# BMS_Slave_Top.net
KiCad netlist of a schematic drawn in Altium Designer
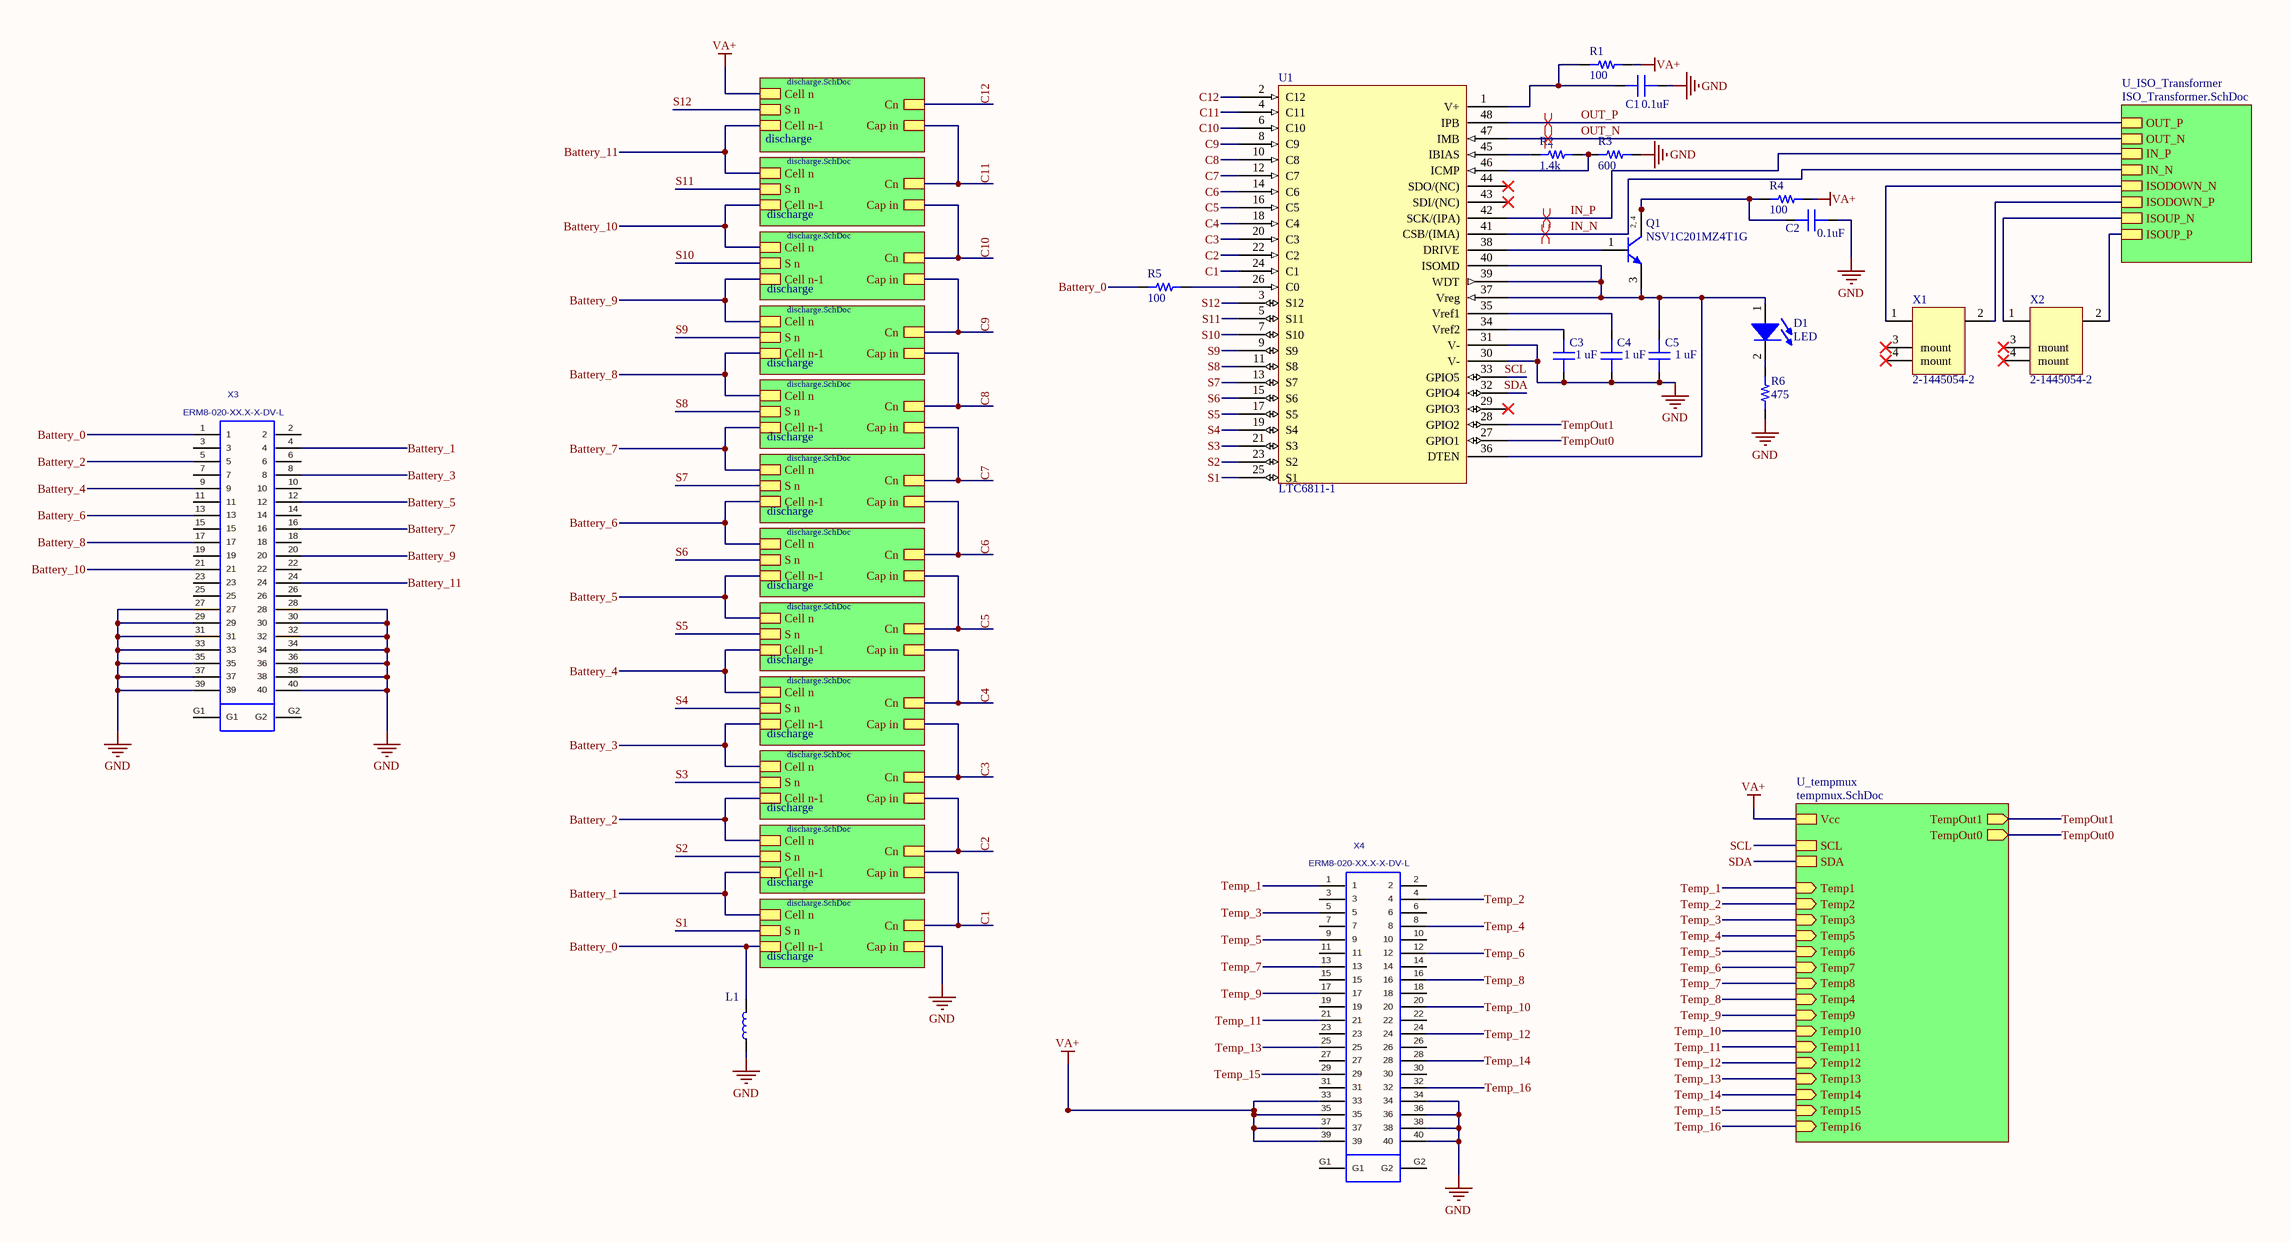
[diagram p0: BMS_Slave_Top.SchDoc]

(export (version "E")
  (design (tool "Eeschema 10.0.6"))
  (components
    (comp (ref "C1")
      (value "capacitor")
      (footprint "0603")
      (description "Generic 0603 capacitor")
      (fields (field (name "CAPACITANCE") "0.1uF") (field (name "VOLTAGE") "50"))
      (libsource (lib "altlib") (part "capacitor"))
    )
    (comp (ref "C2")
      (value "capacitor")
      (footprint "0603")
      (description "Generic 0603 capacitor")
      (fields (field (name "CAPACITANCE") "0.1uF") (field (name "VOLTAGE") "50"))
      (libsource (lib "altlib") (part "capacitor"))
    )
    (comp (ref "C3")
      (value "capacitor")
      (footprint "0603")
      (description "Generic 0603 capacitor")
      (fields (field (name "CAPACITANCE") "1 uF") (field (name "VOLTAGE") "50"))
      (libsource (lib "altlib") (part "capacitor"))
    )
    (comp (ref "C4")
      (value "capacitor")
      (footprint "0603")
      (description "Generic 0603 capacitor")
      (fields (field (name "CAPACITANCE") "1 uF") (field (name "VOLTAGE") "50"))
      (libsource (lib "altlib") (part "capacitor"))
    )
    (comp (ref "C5")
      (value "capacitor")
      (footprint "0603")
      (description "Generic 0603 capacitor")
      (fields (field (name "CAPACITANCE") "1 uF") (field (name "VOLTAGE") "50"))
      (libsource (lib "altlib") (part "capacitor"))
    )
    (comp (ref "D1")
      (value "LED")
      (footprint "0805_LED")
      (description "Generic 0805 LED")
      (libsource (lib "altlib") (part "LED"))
    )
    (comp (ref "L1")
      (value "MPZ1608S221ATA00")
      (footprint "0603")
      (description "220 Ohms @ 100MHz 1 Power Line Ferrite Bead 0")
      (fields
        (field (name "DIGI-KEY_PART_NUMBER") "445-1565-1-ND")
        (field (name "MF") "TDK")
        (field (name "CREATEDBY") "Kevin")
      )
      (libsource (lib "altlib") (part "MPZ1608S221ATA00"))
    )
    (comp (ref "Q1")
      (value "NSV1C201MZ4T1G")
      (footprint "ONSC-SOT-223-4-318E-04_V")
      (fields (field (name "MANUFACTURER") "On Semiconductor") (field (name "CREATEDBY") "J.Childers"))
      (libsource (lib "altlib") (part "CMP-1048-00450-1"))
    )
    (comp (ref "R1")
      (value "100")
      (footprint "RES 0603/1608")
      (fields (field (name "RESISTANCE") "100"))
      (libsource (lib "altlib") (part "Resistor"))
    )
    (comp (ref "R2")
      (value "1.4k")
      (footprint "RES 0603/1608")
      (fields (field (name "RESISTANCE") "1.4k"))
      (libsource (lib "altlib") (part "Resistor"))
    )
    (comp (ref "R3")
      (value "600")
      (footprint "RES 0603/1608")
      (fields (field (name "RESISTANCE") "600"))
      (libsource (lib "altlib") (part "Resistor"))
    )
    (comp (ref "R4")
      (value "100")
      (footprint "RES 0603/1608")
      (fields (field (name "RESISTANCE") "100"))
      (libsource (lib "altlib") (part "Resistor"))
    )
    (comp (ref "R5")
      (value "100")
      (footprint "RES 0603/1608")
      (fields (field (name "RESISTANCE") "100"))
      (libsource (lib "altlib") (part "Resistor"))
    )
    (comp (ref "R6")
      (value "475")
      (footprint "RES 0603/1608")
      (fields (field (name "RESISTANCE") "475"))
      (libsource (lib "altlib") (part "Resistor"))
    )
    (comp (ref "U1")
      (value "LTC6811-1")
      (footprint "LTC6811-1")
      (libsource (lib "altlib") (part "LTC6811-1"))
    )
    (comp (ref "X1")
      (value "2-1445054-2")
      (footprint "2-1445054-2")
      (description "Micro MATE-N-LOK 1x2")
      (libsource (lib "altlib") (part "2-1445054-2"))
    )
    (comp (ref "X2")
      (value "2-1445054-2")
      (footprint "2-1445054-2")
      (description "Micro MATE-N-LOK 1x2")
      (libsource (lib "altlib") (part "2-1445054-2"))
    )
    (comp (ref "X3")
      (value "ERM8-020-XX.X-X-DV-L")
      (footprint "ERM8-020-XX.X-X-DV-L")
      (fields (field (name "MANUFACTURER") "SAMTEC") (field (name "CREATED") "August 17, 2016 - Wendy Xin"))
      (libsource (lib "altlib") (part "ERM8-020-XX.X-X-DV-L"))
    )
    (comp (ref "X4")
      (value "ERM8-020-XX.X-X-DV-L")
      (footprint "ERM8-020-XX.X-X-DV-L")
      (fields (field (name "MANUFACTURER") "SAMTEC") (field (name "CREATED") "August 17, 2016 - Wendy Xin"))
      (libsource (lib "altlib") (part "ERM8-020-XX.X-X-DV-L"))
    )
  )
  (nets
    (net (code "1") (name "/Battery_0") (class "Default")
      (node (ref "L1") (pin "2") (pinfunction "2_2") (pintype "passive"))
      (node (ref "R5") (pin "1") (pinfunction "1_1") (pintype "passive"))
      (node (ref "X3") (pin "1") (pinfunction "1_1") (pintype "passive"))
    )
    (net (code "2") (name "/Battery_1") (class "Default")
      (node (ref "X3") (pin "4") (pinfunction "4_4") (pintype "passive"))
    )
    (net (code "3") (name "/Battery_2") (class "Default")
      (node (ref "X3") (pin "5") (pinfunction "5_5") (pintype "passive"))
    )
    (net (code "4") (name "/Battery_3") (class "Default")
      (node (ref "X3") (pin "8") (pinfunction "8_8") (pintype "passive"))
    )
    (net (code "5") (name "/Battery_4") (class "Default")
      (node (ref "X3") (pin "9") (pinfunction "9_9") (pintype "passive"))
    )
    (net (code "6") (name "/Battery_5") (class "Default")
      (node (ref "X3") (pin "12") (pinfunction "12_12") (pintype "passive"))
    )
    (net (code "7") (name "/Battery_6") (class "Default")
      (node (ref "X3") (pin "13") (pinfunction "13_13") (pintype "passive"))
    )
    (net (code "8") (name "/Battery_7") (class "Default")
      (node (ref "X3") (pin "16") (pinfunction "16_16") (pintype "passive"))
    )
    (net (code "9") (name "/Battery_8") (class "Default")
      (node (ref "X3") (pin "17") (pinfunction "17_17") (pintype "passive"))
    )
    (net (code "10") (name "/Battery_9") (class "Default")
      (node (ref "X3") (pin "20") (pinfunction "20_20") (pintype "passive"))
    )
    (net (code "11") (name "/Battery_10") (class "Default")
      (node (ref "X3") (pin "21") (pinfunction "21_21") (pintype "passive"))
    )
    (net (code "12") (name "/Battery_11") (class "Default")
      (node (ref "X3") (pin "24") (pinfunction "24_24") (pintype "passive"))
    )
    (net (code "13") (name "/C1") (class "Default")
      (node (ref "U1") (pin "24") (pinfunction "C1_24") (pintype "input"))
    )
    (net (code "14") (name "/C2") (class "Default")
      (node (ref "U1") (pin "22") (pinfunction "C2_22") (pintype "input"))
    )
    (net (code "15") (name "/C3") (class "Default")
      (node (ref "U1") (pin "20") (pinfunction "C3_20") (pintype "input"))
    )
    (net (code "16") (name "/C4") (class "Default")
      (node (ref "U1") (pin "18") (pinfunction "C4_18") (pintype "input"))
    )
    (net (code "17") (name "/C5") (class "Default")
      (node (ref "U1") (pin "16") (pinfunction "C5_16") (pintype "input"))
    )
    (net (code "18") (name "/C6") (class "Default")
      (node (ref "U1") (pin "14") (pinfunction "C6_14") (pintype "input"))
    )
    (net (code "19") (name "/C7") (class "Default")
      (node (ref "U1") (pin "12") (pinfunction "C7_12") (pintype "input"))
    )
    (net (code "20") (name "/C8") (class "Default")
      (node (ref "U1") (pin "10") (pinfunction "C8_10") (pintype "input"))
    )
    (net (code "21") (name "/C9") (class "Default")
      (node (ref "U1") (pin "8") (pinfunction "C9_8") (pintype "input"))
    )
    (net (code "22") (name "/C10") (class "Default")
      (node (ref "U1") (pin "6") (pinfunction "C10_6") (pintype "input"))
    )
    (net (code "23") (name "/C11") (class "Default")
      (node (ref "U1") (pin "4") (pinfunction "C11_4") (pintype "input"))
    )
    (net (code "24") (name "/C12") (class "Default")
      (node (ref "U1") (pin "2") (pinfunction "C12_2") (pintype "input"))
    )
    (net (code "25") (name "/IN_N") (class "Default")
      (node (ref "U1") (pin "41") (pinfunction "CSB/(IMA)_41") (pintype "passive"))
    )
    (net (code "26") (name "/IN_P") (class "Default")
      (node (ref "U1") (pin "42") (pinfunction "SCK/(IPA)_42") (pintype "passive"))
    )
    (net (code "27") (name "/ISODOWN_N") (class "Default") (node (ref "X1") (pin "1") (pintype "power_in")))
    (net (code "28") (name "/ISODOWN_P") (class "Default") (node (ref "X1") (pin "2") (pintype "power_in")))
    (net (code "29") (name "/ISOUP_N") (class "Default") (node (ref "X2") (pin "1") (pintype "power_in")))
    (net (code "30") (name "/ISOUP_P") (class "Default") (node (ref "X2") (pin "2") (pintype "power_in")))
    (net (code "31") (name "/OUT_N") (class "Default")
      (node (ref "U1") (pin "47") (pinfunction "IMB_47") (pintype "input"))
    )
    (net (code "32") (name "/OUT_P") (class "Default")
      (node (ref "U1") (pin "48") (pinfunction "IPB_48") (pintype "passive"))
    )
    (net (code "33") (name "/S1") (class "Default")
      (node (ref "U1") (pin "25") (pinfunction "S1_25") (pintype "bidirectional"))
    )
    (net (code "34") (name "/S2") (class "Default")
      (node (ref "U1") (pin "23") (pinfunction "S2_23") (pintype "bidirectional"))
    )
    (net (code "35") (name "/S3") (class "Default")
      (node (ref "U1") (pin "21") (pinfunction "S3_21") (pintype "bidirectional"))
    )
    (net (code "36") (name "/S4") (class "Default")
      (node (ref "U1") (pin "19") (pinfunction "S4_19") (pintype "bidirectional"))
    )
    (net (code "37") (name "/S5") (class "Default")
      (node (ref "U1") (pin "17") (pinfunction "S5_17") (pintype "bidirectional"))
    )
    (net (code "38") (name "/S6") (class "Default")
      (node (ref "U1") (pin "15") (pinfunction "S6_15") (pintype "bidirectional"))
    )
    (net (code "39") (name "/S7") (class "Default")
      (node (ref "U1") (pin "13") (pinfunction "S7_13") (pintype "bidirectional"))
    )
    (net (code "40") (name "/S8") (class "Default")
      (node (ref "U1") (pin "11") (pinfunction "S8_11") (pintype "bidirectional"))
    )
    (net (code "41") (name "/S9") (class "Default")
      (node (ref "U1") (pin "9") (pinfunction "S9_9") (pintype "bidirectional"))
    )
    (net (code "42") (name "/S10") (class "Default")
      (node (ref "U1") (pin "7") (pinfunction "S10_7") (pintype "bidirectional"))
    )
    (net (code "43") (name "/S11") (class "Default")
      (node (ref "U1") (pin "5") (pinfunction "S11_5") (pintype "bidirectional"))
    )
    (net (code "44") (name "/S12") (class "Default")
      (node (ref "U1") (pin "3") (pinfunction "S12_3") (pintype "bidirectional"))
    )
    (net (code "45") (name "/SCL") (class "Default")
      (node (ref "U1") (pin "33") (pinfunction "GPIO5_33") (pintype "bidirectional"))
    )
    (net (code "46") (name "/SDA") (class "Default")
      (node (ref "U1") (pin "32") (pinfunction "GPIO4_32") (pintype "bidirectional"))
    )
    (net (code "47") (name "/TempOut0") (class "Default")
      (node (ref "U1") (pin "27") (pinfunction "GPIO1_27") (pintype "bidirectional"))
    )
    (net (code "48") (name "/TempOut1") (class "Default")
      (node (ref "U1") (pin "28") (pinfunction "GPIO2_28") (pintype "bidirectional"))
    )
    (net (code "49") (name "/Temp_1") (class "Default")
      (node (ref "X4") (pin "1") (pinfunction "1_1") (pintype "passive"))
    )
    (net (code "50") (name "/Temp_2") (class "Default")
      (node (ref "X4") (pin "4") (pinfunction "4_4") (pintype "passive"))
    )
    (net (code "51") (name "/Temp_3") (class "Default")
      (node (ref "X4") (pin "5") (pinfunction "5_5") (pintype "passive"))
    )
    (net (code "52") (name "/Temp_4") (class "Default")
      (node (ref "X4") (pin "8") (pinfunction "8_8") (pintype "passive"))
    )
    (net (code "53") (name "/Temp_5") (class "Default")
      (node (ref "X4") (pin "9") (pinfunction "9_9") (pintype "passive"))
    )
    (net (code "54") (name "/Temp_6") (class "Default")
      (node (ref "X4") (pin "12") (pinfunction "12_12") (pintype "passive"))
    )
    (net (code "55") (name "/Temp_7") (class "Default")
      (node (ref "X4") (pin "13") (pinfunction "13_13") (pintype "passive"))
    )
    (net (code "56") (name "/Temp_8") (class "Default")
      (node (ref "X4") (pin "16") (pinfunction "16_16") (pintype "passive"))
    )
    (net (code "57") (name "/Temp_9") (class "Default")
      (node (ref "X4") (pin "17") (pinfunction "17_17") (pintype "passive"))
    )
    (net (code "58") (name "/Temp_10") (class "Default")
      (node (ref "X4") (pin "20") (pinfunction "20_20") (pintype "passive"))
    )
    (net (code "59") (name "/Temp_11") (class "Default")
      (node (ref "X4") (pin "21") (pinfunction "21_21") (pintype "passive"))
    )
    (net (code "60") (name "/Temp_12") (class "Default")
      (node (ref "X4") (pin "24") (pinfunction "24_24") (pintype "passive"))
    )
    (net (code "61") (name "/Temp_13") (class "Default")
      (node (ref "X4") (pin "25") (pinfunction "25_25") (pintype "passive"))
    )
    (net (code "62") (name "/Temp_14") (class "Default")
      (node (ref "X4") (pin "28") (pinfunction "28_28") (pintype "passive"))
    )
    (net (code "63") (name "/Temp_15") (class "Default")
      (node (ref "X4") (pin "29") (pinfunction "29_29") (pintype "passive"))
    )
    (net (code "64") (name "/Temp_16") (class "Default")
      (node (ref "X4") (pin "32") (pinfunction "32_32") (pintype "passive"))
    )
    (net (code "65") (name "GND") (class "Default")
      (node (ref "C1") (pin "1") (pinfunction "1_1") (pintype "passive"))
      (node (ref "C2") (pin "1") (pinfunction "1_1") (pintype "passive"))
      (node (ref "C3") (pin "1") (pinfunction "1_1") (pintype "passive"))
      (node (ref "C4") (pin "1") (pinfunction "1_1") (pintype "passive"))
      (node (ref "C5") (pin "1") (pinfunction "1_1") (pintype "passive"))
      (node (ref "L1") (pin "1") (pinfunction "1_1") (pintype "passive"))
      (node (ref "R3") (pin "2") (pinfunction "2_2") (pintype "passive"))
      (node (ref "R6") (pin "1") (pinfunction "1_1") (pintype "passive"))
      (node (ref "U1") (pin "30") (pinfunction "V-_30") (pintype "power_in"))
      (node (ref "U1") (pin "31") (pinfunction "V-_31") (pintype "power_in"))
      (node (ref "X3") (pin "27") (pinfunction "27_27") (pintype "passive"))
      (node (ref "X3") (pin "28") (pinfunction "28_28") (pintype "passive"))
      (node (ref "X3") (pin "29") (pinfunction "29_29") (pintype "passive"))
      (node (ref "X3") (pin "30") (pinfunction "30_30") (pintype "passive"))
      (node (ref "X3") (pin "31") (pinfunction "31_31") (pintype "passive"))
      (node (ref "X3") (pin "32") (pinfunction "32_32") (pintype "passive"))
      (node (ref "X3") (pin "33") (pinfunction "33_33") (pintype "passive"))
      (node (ref "X3") (pin "34") (pinfunction "34_34") (pintype "passive"))
      (node (ref "X3") (pin "35") (pinfunction "35_35") (pintype "passive"))
      (node (ref "X3") (pin "36") (pinfunction "36_36") (pintype "passive"))
      (node (ref "X3") (pin "37") (pinfunction "37_37") (pintype "passive"))
      (node (ref "X3") (pin "38") (pinfunction "38_38") (pintype "passive"))
      (node (ref "X3") (pin "39") (pinfunction "39_39") (pintype "passive"))
      (node (ref "X3") (pin "40") (pinfunction "40_40") (pintype "passive"))
      (node (ref "X4") (pin "34") (pinfunction "34_34") (pintype "passive"))
      (node (ref "X4") (pin "36") (pinfunction "36_36") (pintype "passive"))
      (node (ref "X4") (pin "38") (pinfunction "38_38") (pintype "passive"))
      (node (ref "X4") (pin "40") (pinfunction "40_40") (pintype "passive"))
    )
    (net (code "66") (name "Net-(C2-Pad2)") (class "Default")
      (node (ref "C2") (pin "2") (pinfunction "2_2") (pintype "passive"))
      (node (ref "Q1") (pin "2") (pinfunction "C_2") (pintype "passive"))
      (node (ref "Q1") (pin "4") (pinfunction "C_4") (pintype "passive"))
      (node (ref "R4") (pin "2") (pinfunction "2_2") (pintype "passive"))
    )
    (net (code "67") (name "Net-(D1-A)") (class "Default")
      (node (ref "C5") (pin "2") (pinfunction "2_2") (pintype "passive"))
      (node (ref "D1") (pin "1") (pinfunction "A_1") (pintype "passive"))
      (node (ref "Q1") (pin "3") (pinfunction "E_3") (pintype "passive"))
      (node (ref "U1") (pin "36") (pinfunction "DTEN_36") (pintype "passive"))
      (node (ref "U1") (pin "37") (pinfunction "Vreg_37") (pintype "input"))
      (node (ref "U1") (pin "39") (pinfunction "WDT_39") (pintype "output"))
      (node (ref "U1") (pin "40") (pinfunction "ISOMD_40") (pintype "passive"))
    )
    (net (code "68") (name "Net-(D1-K)") (class "Default")
      (node (ref "D1") (pin "2") (pinfunction "K_2") (pintype "passive"))
      (node (ref "R6") (pin "2") (pinfunction "2_2") (pintype "passive"))
    )
    (net (code "69") (name "Net-(Q1-B)") (class "Default")
      (node (ref "Q1") (pin "1") (pinfunction "B_1") (pintype "passive"))
      (node (ref "U1") (pin "38") (pinfunction "DRIVE_38") (pintype "passive"))
    )
    (net (code "70") (name "Net-(U1-C0)") (class "Default")
      (node (ref "R5") (pin "2") (pinfunction "2_2") (pintype "passive"))
      (node (ref "U1") (pin "26") (pinfunction "C0_26") (pintype "input"))
    )
    (net (code "71") (name "Net-(U1-IBIAS)") (class "Default")
      (node (ref "R2") (pin "1") (pinfunction "1_1") (pintype "passive"))
      (node (ref "U1") (pin "45") (pinfunction "IBIAS_45") (pintype "input"))
    )
    (net (code "72") (name "Net-(U1-ICMP)") (class "Default")
      (node (ref "R2") (pin "2") (pinfunction "2_2") (pintype "passive"))
      (node (ref "R3") (pin "1") (pinfunction "1_1") (pintype "passive"))
      (node (ref "U1") (pin "46") (pinfunction "ICMP_46") (pintype "input"))
    )
    (net (code "73") (name "Net-(U1-V+)") (class "Default")
      (node (ref "C1") (pin "2") (pinfunction "2_2") (pintype "passive"))
      (node (ref "R1") (pin "2") (pinfunction "2_2") (pintype "passive"))
      (node (ref "U1") (pin "1") (pinfunction "V+_1") (pintype "power_in"))
    )
    (net (code "74") (name "Net-(U1-Vref1)") (class "Default")
      (node (ref "C4") (pin "2") (pinfunction "2_2") (pintype "passive"))
      (node (ref "U1") (pin "35") (pinfunction "Vref1_35") (pintype "passive"))
    )
    (net (code "75") (name "Net-(U1-Vref2)") (class "Default")
      (node (ref "C3") (pin "2") (pinfunction "2_2") (pintype "passive"))
      (node (ref "U1") (pin "34") (pinfunction "Vref2_34") (pintype "passive"))
    )
    (net (code "76") (name "VA+") (class "Default")
      (node (ref "R1") (pin "1") (pinfunction "1_1") (pintype "passive"))
      (node (ref "R4") (pin "1") (pinfunction "1_1") (pintype "passive"))
      (node (ref "X4") (pin "33") (pinfunction "33_33") (pintype "passive"))
      (node (ref "X4") (pin "35") (pinfunction "35_35") (pintype "passive"))
      (node (ref "X4") (pin "37") (pinfunction "37_37") (pintype "passive"))
      (node (ref "X4") (pin "39") (pinfunction "39_39") (pintype "passive"))
    )
    (net (code "77") (name "unconnected-(U1-GPIO3-Pad29)") (class "Default")
      (node (ref "U1") (pin "29") (pinfunction "GPIO3_29") (pintype "bidirectional+no_connect"))
    )
    (net (code "78") (name "unconnected-(U1-SDI{slash}(NC)-Pad43)") (class "Default")
      (node (ref "U1") (pin "43") (pinfunction "SDI/(NC)_43") (pintype "passive+no_connect"))
    )
    (net (code "79") (name "unconnected-(U1-SDO{slash}(NC)-Pad44)") (class "Default")
      (node (ref "U1") (pin "44") (pinfunction "SDO/(NC)_44") (pintype "passive+no_connect"))
    )
    (net (code "80") (name "unconnected-(X1-mount-Pad3)") (class "Default")
      (node (ref "X1") (pin "3") (pinfunction "mount_3") (pintype "power_in+no_connect"))
    )
    (net (code "81") (name "unconnected-(X1-mount-Pad4)") (class "Default")
      (node (ref "X1") (pin "4") (pinfunction "mount_4") (pintype "power_in+no_connect"))
    )
    (net (code "82") (name "unconnected-(X2-mount-Pad3)") (class "Default")
      (node (ref "X2") (pin "3") (pinfunction "mount_3") (pintype "power_in+no_connect"))
    )
    (net (code "83") (name "unconnected-(X2-mount-Pad4)") (class "Default")
      (node (ref "X2") (pin "4") (pinfunction "mount_4") (pintype "power_in+no_connect"))
    )
    (net (code "84") (name "unconnected-(X3-Pad2)") (class "Default")
      (node (ref "X3") (pin "2") (pinfunction "2_2") (pintype "passive"))
    )
    (net (code "85") (name "unconnected-(X3-Pad3)") (class "Default")
      (node (ref "X3") (pin "3") (pinfunction "3_3") (pintype "passive"))
    )
    (net (code "86") (name "unconnected-(X3-Pad6)") (class "Default")
      (node (ref "X3") (pin "6") (pinfunction "6_6") (pintype "passive"))
    )
    (net (code "87") (name "unconnected-(X3-Pad7)") (class "Default")
      (node (ref "X3") (pin "7") (pinfunction "7_7") (pintype "passive"))
    )
    (net (code "88") (name "unconnected-(X3-Pad10)") (class "Default")
      (node (ref "X3") (pin "10") (pinfunction "10_10") (pintype "passive"))
    )
    (net (code "89") (name "unconnected-(X3-Pad11)") (class "Default")
      (node (ref "X3") (pin "11") (pinfunction "11_11") (pintype "passive"))
    )
    (net (code "90") (name "unconnected-(X3-Pad14)") (class "Default")
      (node (ref "X3") (pin "14") (pinfunction "14_14") (pintype "passive"))
    )
    (net (code "91") (name "unconnected-(X3-Pad15)") (class "Default")
      (node (ref "X3") (pin "15") (pinfunction "15_15") (pintype "passive"))
    )
    (net (code "92") (name "unconnected-(X3-Pad18)") (class "Default")
      (node (ref "X3") (pin "18") (pinfunction "18_18") (pintype "passive"))
    )
    (net (code "93") (name "unconnected-(X3-Pad19)") (class "Default")
      (node (ref "X3") (pin "19") (pinfunction "19_19") (pintype "passive"))
    )
    (net (code "94") (name "unconnected-(X3-Pad22)") (class "Default")
      (node (ref "X3") (pin "22") (pinfunction "22_22") (pintype "passive"))
    )
    (net (code "95") (name "unconnected-(X3-Pad23)") (class "Default")
      (node (ref "X3") (pin "23") (pinfunction "23_23") (pintype "passive"))
    )
    (net (code "96") (name "unconnected-(X3-Pad25)") (class "Default")
      (node (ref "X3") (pin "25") (pinfunction "25_25") (pintype "passive"))
    )
    (net (code "97") (name "unconnected-(X3-Pad26)") (class "Default")
      (node (ref "X3") (pin "26") (pinfunction "26_26") (pintype "passive"))
    )
    (net (code "98") (name "unconnected-(X3-PadG1)") (class "Default")
      (node (ref "X3") (pin "G1") (pinfunction "G1_G1") (pintype "passive"))
    )
    (net (code "99") (name "unconnected-(X3-PadG2)") (class "Default")
      (node (ref "X3") (pin "G2") (pinfunction "G2_G2") (pintype "passive"))
    )
    (net (code "100") (name "unconnected-(X4-Pad2)") (class "Default")
      (node (ref "X4") (pin "2") (pinfunction "2_2") (pintype "passive"))
    )
    (net (code "101") (name "unconnected-(X4-Pad3)") (class "Default")
      (node (ref "X4") (pin "3") (pinfunction "3_3") (pintype "passive"))
    )
    (net (code "102") (name "unconnected-(X4-Pad6)") (class "Default")
      (node (ref "X4") (pin "6") (pinfunction "6_6") (pintype "passive"))
    )
    (net (code "103") (name "unconnected-(X4-Pad7)") (class "Default")
      (node (ref "X4") (pin "7") (pinfunction "7_7") (pintype "passive"))
    )
    (net (code "104") (name "unconnected-(X4-Pad10)") (class "Default")
      (node (ref "X4") (pin "10") (pinfunction "10_10") (pintype "passive"))
    )
    (net (code "105") (name "unconnected-(X4-Pad11)") (class "Default")
      (node (ref "X4") (pin "11") (pinfunction "11_11") (pintype "passive"))
    )
    (net (code "106") (name "unconnected-(X4-Pad14)") (class "Default")
      (node (ref "X4") (pin "14") (pinfunction "14_14") (pintype "passive"))
    )
    (net (code "107") (name "unconnected-(X4-Pad15)") (class "Default")
      (node (ref "X4") (pin "15") (pinfunction "15_15") (pintype "passive"))
    )
    (net (code "108") (name "unconnected-(X4-Pad18)") (class "Default")
      (node (ref "X4") (pin "18") (pinfunction "18_18") (pintype "passive"))
    )
    (net (code "109") (name "unconnected-(X4-Pad19)") (class "Default")
      (node (ref "X4") (pin "19") (pinfunction "19_19") (pintype "passive"))
    )
    (net (code "110") (name "unconnected-(X4-Pad22)") (class "Default")
      (node (ref "X4") (pin "22") (pinfunction "22_22") (pintype "passive"))
    )
    (net (code "111") (name "unconnected-(X4-Pad23)") (class "Default")
      (node (ref "X4") (pin "23") (pinfunction "23_23") (pintype "passive"))
    )
    (net (code "112") (name "unconnected-(X4-Pad26)") (class "Default")
      (node (ref "X4") (pin "26") (pinfunction "26_26") (pintype "passive"))
    )
    (net (code "113") (name "unconnected-(X4-Pad27)") (class "Default")
      (node (ref "X4") (pin "27") (pinfunction "27_27") (pintype "passive"))
    )
    (net (code "114") (name "unconnected-(X4-Pad30)") (class "Default")
      (node (ref "X4") (pin "30") (pinfunction "30_30") (pintype "passive"))
    )
    (net (code "115") (name "unconnected-(X4-Pad31)") (class "Default")
      (node (ref "X4") (pin "31") (pinfunction "31_31") (pintype "passive"))
    )
    (net (code "116") (name "unconnected-(X4-PadG1)") (class "Default")
      (node (ref "X4") (pin "G1") (pinfunction "G1_G1") (pintype "passive"))
    )
    (net (code "117") (name "unconnected-(X4-PadG2)") (class "Default")
      (node (ref "X4") (pin "G2") (pinfunction "G2_G2") (pintype "passive"))
    )
  )
)
